# LED-Wiring.net
KiCad netlist of a schematic drawn in EAGLE
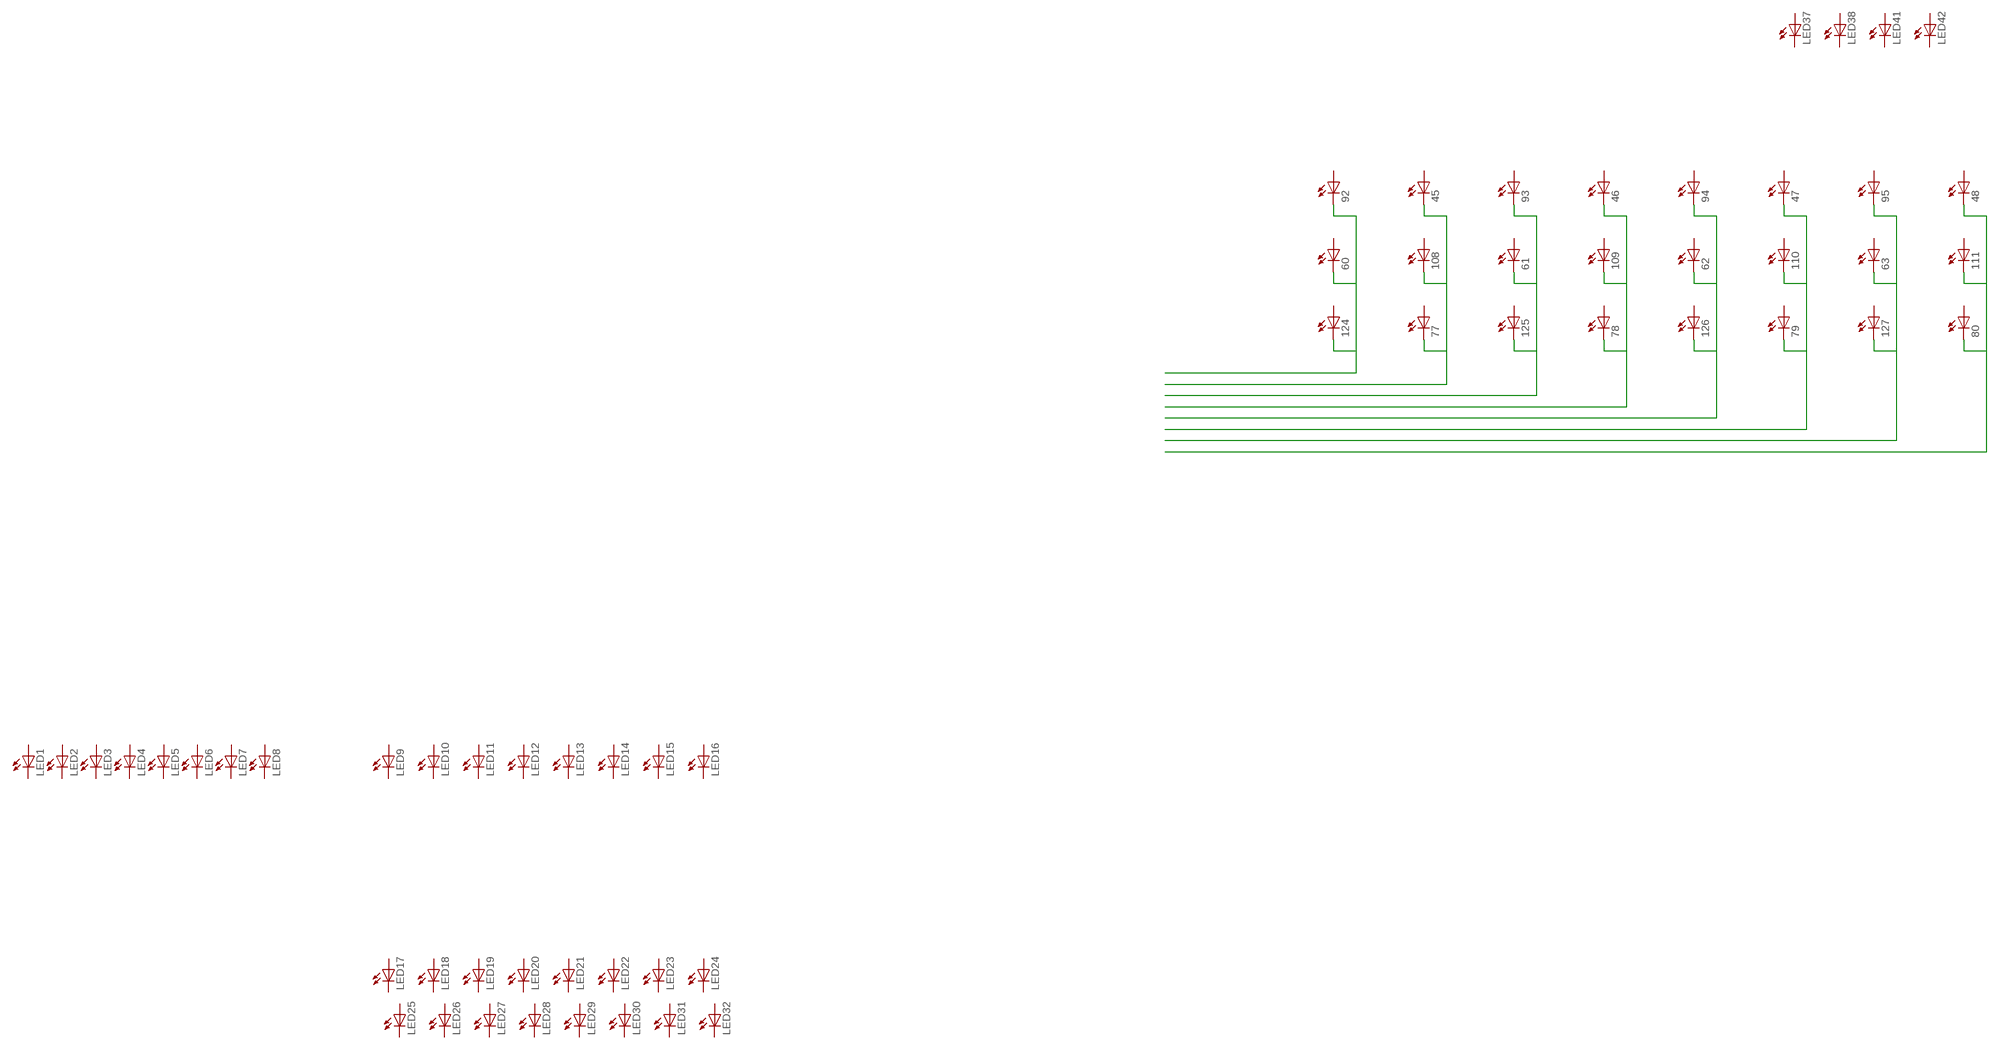
[diagram p0: schematic, sheet 1]

(export (version "E")
  (design (tool "Eeschema 10.0.6"))
  (components
    (comp (ref "45")
      (value "LED")
      (footprint "eagle-import:SMARTLED-TTW")
      (libsource (lib "eagle-import") (part "LED"))
    )
    (comp (ref "46")
      (value "LED")
      (footprint "eagle-import:SMARTLED-TTW")
      (libsource (lib "eagle-import") (part "LED"))
    )
    (comp (ref "47")
      (value "LED")
      (footprint "eagle-import:SMARTLED-TTW")
      (libsource (lib "eagle-import") (part "LED"))
    )
    (comp (ref "48")
      (value "LED")
      (footprint "eagle-import:SMARTLED-TTW")
      (libsource (lib "eagle-import") (part "LED"))
    )
    (comp (ref "60")
      (value "LED")
      (footprint "eagle-import:SMARTLED-TTW")
      (libsource (lib "eagle-import") (part "LED"))
    )
    (comp (ref "61")
      (value "LED")
      (footprint "eagle-import:SMARTLED-TTW")
      (libsource (lib "eagle-import") (part "LED"))
    )
    (comp (ref "62")
      (value "LED")
      (footprint "eagle-import:SMARTLED-TTW")
      (libsource (lib "eagle-import") (part "LED"))
    )
    (comp (ref "63")
      (value "LED")
      (footprint "eagle-import:SMARTLED-TTW")
      (libsource (lib "eagle-import") (part "LED"))
    )
    (comp (ref "77")
      (value "LED")
      (footprint "eagle-import:SMARTLED-TTW")
      (libsource (lib "eagle-import") (part "LED"))
    )
    (comp (ref "78")
      (value "LED")
      (footprint "eagle-import:SMARTLED-TTW")
      (libsource (lib "eagle-import") (part "LED"))
    )
    (comp (ref "79")
      (value "LED")
      (footprint "eagle-import:SMARTLED-TTW")
      (libsource (lib "eagle-import") (part "LED"))
    )
    (comp (ref "80")
      (value "LED")
      (footprint "eagle-import:SMARTLED-TTW")
      (libsource (lib "eagle-import") (part "LED"))
    )
    (comp (ref "92")
      (value "LED")
      (footprint "eagle-import:SMARTLED-TTW")
      (libsource (lib "eagle-import") (part "LED"))
    )
    (comp (ref "93")
      (value "LED")
      (footprint "eagle-import:SMARTLED-TTW")
      (libsource (lib "eagle-import") (part "LED"))
    )
    (comp (ref "94")
      (value "LED")
      (footprint "eagle-import:SMARTLED-TTW")
      (libsource (lib "eagle-import") (part "LED"))
    )
    (comp (ref "95")
      (value "LED")
      (footprint "eagle-import:SMARTLED-TTW")
      (libsource (lib "eagle-import") (part "LED"))
    )
    (comp (ref "108")
      (value "LED")
      (footprint "eagle-import:SMARTLED-TTW")
      (libsource (lib "eagle-import") (part "LED"))
    )
    (comp (ref "109")
      (value "LED")
      (footprint "eagle-import:SMARTLED-TTW")
      (libsource (lib "eagle-import") (part "LED"))
    )
    (comp (ref "110")
      (value "LED")
      (footprint "eagle-import:SMARTLED-TTW")
      (libsource (lib "eagle-import") (part "LED"))
    )
    (comp (ref "111")
      (value "LED")
      (footprint "eagle-import:SMARTLED-TTW")
      (libsource (lib "eagle-import") (part "LED"))
    )
    (comp (ref "124")
      (value "LED")
      (footprint "eagle-import:SMARTLED-TTW")
      (libsource (lib "eagle-import") (part "LED"))
    )
    (comp (ref "125")
      (value "LED")
      (footprint "eagle-import:SMARTLED-TTW")
      (libsource (lib "eagle-import") (part "LED"))
    )
    (comp (ref "126")
      (value "LED")
      (footprint "eagle-import:SMARTLED-TTW")
      (libsource (lib "eagle-import") (part "LED"))
    )
    (comp (ref "127")
      (value "LED")
      (footprint "eagle-import:SMARTLED-TTW")
      (libsource (lib "eagle-import") (part "LED"))
    )
    (comp (ref "LED1")
      (value "LED")
      (footprint "eagle-import:SMARTLED-TTW")
      (libsource (lib "eagle-import") (part "LED"))
    )
    (comp (ref "LED2")
      (value "LED")
      (footprint "eagle-import:SMARTLED-TTW")
      (libsource (lib "eagle-import") (part "LED"))
    )
    (comp (ref "LED3")
      (value "LED")
      (footprint "eagle-import:SMARTLED-TTW")
      (libsource (lib "eagle-import") (part "LED"))
    )
    (comp (ref "LED4")
      (value "LED")
      (footprint "eagle-import:SMARTLED-TTW")
      (libsource (lib "eagle-import") (part "LED"))
    )
    (comp (ref "LED5")
      (value "LED")
      (footprint "eagle-import:SMARTLED-TTW")
      (libsource (lib "eagle-import") (part "LED"))
    )
    (comp (ref "LED6")
      (value "LED")
      (footprint "eagle-import:SMARTLED-TTW")
      (libsource (lib "eagle-import") (part "LED"))
    )
    (comp (ref "LED7")
      (value "LED")
      (footprint "eagle-import:SMARTLED-TTW")
      (libsource (lib "eagle-import") (part "LED"))
    )
    (comp (ref "LED8")
      (value "LED")
      (footprint "eagle-import:SMARTLED-TTW")
      (libsource (lib "eagle-import") (part "LED"))
    )
    (comp (ref "LED9")
      (value "LED")
      (footprint "eagle-import:SMARTLED-TTW")
      (libsource (lib "eagle-import") (part "LED"))
    )
    (comp (ref "LED10")
      (value "LED")
      (footprint "eagle-import:SMARTLED-TTW")
      (libsource (lib "eagle-import") (part "LED"))
    )
    (comp (ref "LED11")
      (value "LED")
      (footprint "eagle-import:SMARTLED-TTW")
      (libsource (lib "eagle-import") (part "LED"))
    )
    (comp (ref "LED12")
      (value "LED")
      (footprint "eagle-import:SMARTLED-TTW")
      (libsource (lib "eagle-import") (part "LED"))
    )
    (comp (ref "LED13")
      (value "LED")
      (footprint "eagle-import:SMARTLED-TTW")
      (libsource (lib "eagle-import") (part "LED"))
    )
    (comp (ref "LED14")
      (value "LED")
      (footprint "eagle-import:SMARTLED-TTW")
      (libsource (lib "eagle-import") (part "LED"))
    )
    (comp (ref "LED15")
      (value "LED")
      (footprint "eagle-import:SMARTLED-TTW")
      (libsource (lib "eagle-import") (part "LED"))
    )
    (comp (ref "LED16")
      (value "LED")
      (footprint "eagle-import:SMARTLED-TTW")
      (libsource (lib "eagle-import") (part "LED"))
    )
    (comp (ref "LED17")
      (value "LED")
      (footprint "eagle-import:SMARTLED-TTW")
      (libsource (lib "eagle-import") (part "LED"))
    )
    (comp (ref "LED18")
      (value "LED")
      (footprint "eagle-import:SMARTLED-TTW")
      (libsource (lib "eagle-import") (part "LED"))
    )
    (comp (ref "LED19")
      (value "LED")
      (footprint "eagle-import:SMARTLED-TTW")
      (libsource (lib "eagle-import") (part "LED"))
    )
    (comp (ref "LED20")
      (value "LED")
      (footprint "eagle-import:SMARTLED-TTW")
      (libsource (lib "eagle-import") (part "LED"))
    )
    (comp (ref "LED21")
      (value "LED")
      (footprint "eagle-import:SMARTLED-TTW")
      (libsource (lib "eagle-import") (part "LED"))
    )
    (comp (ref "LED22")
      (value "LED")
      (footprint "eagle-import:SMARTLED-TTW")
      (libsource (lib "eagle-import") (part "LED"))
    )
    (comp (ref "LED23")
      (value "LED")
      (footprint "eagle-import:SMARTLED-TTW")
      (libsource (lib "eagle-import") (part "LED"))
    )
    (comp (ref "LED24")
      (value "LED")
      (footprint "eagle-import:SMARTLED-TTW")
      (libsource (lib "eagle-import") (part "LED"))
    )
    (comp (ref "LED25")
      (value "LED")
      (footprint "eagle-import:SMARTLED-TTW")
      (libsource (lib "eagle-import") (part "LED"))
    )
    (comp (ref "LED26")
      (value "LED")
      (footprint "eagle-import:SMARTLED-TTW")
      (libsource (lib "eagle-import") (part "LED"))
    )
    (comp (ref "LED27")
      (value "LED")
      (footprint "eagle-import:SMARTLED-TTW")
      (libsource (lib "eagle-import") (part "LED"))
    )
    (comp (ref "LED28")
      (value "LED")
      (footprint "eagle-import:SMARTLED-TTW")
      (libsource (lib "eagle-import") (part "LED"))
    )
    (comp (ref "LED29")
      (value "LED")
      (footprint "eagle-import:SMARTLED-TTW")
      (libsource (lib "eagle-import") (part "LED"))
    )
    (comp (ref "LED30")
      (value "LED")
      (footprint "eagle-import:SMARTLED-TTW")
      (libsource (lib "eagle-import") (part "LED"))
    )
    (comp (ref "LED31")
      (value "LED")
      (footprint "eagle-import:SMARTLED-TTW")
      (libsource (lib "eagle-import") (part "LED"))
    )
    (comp (ref "LED32")
      (value "LED")
      (footprint "eagle-import:SMARTLED-TTW")
      (libsource (lib "eagle-import") (part "LED"))
    )
    (comp (ref "LED37")
      (value "LED")
      (footprint "eagle-import:SMARTLED-TTW")
      (libsource (lib "eagle-import") (part "LED"))
    )
    (comp (ref "LED38")
      (value "LED")
      (footprint "eagle-import:SMARTLED-TTW")
      (libsource (lib "eagle-import") (part "LED"))
    )
    (comp (ref "LED41")
      (value "LED")
      (footprint "eagle-import:SMARTLED-TTW")
      (libsource (lib "eagle-import") (part "LED"))
    )
    (comp (ref "LED42")
      (value "LED")
      (footprint "eagle-import:SMARTLED-TTW")
      (libsource (lib "eagle-import") (part "LED"))
    )
  )
  (nets
    (net (code "1") (name "Net-(108-C)") (class "Default")
      (node (ref "108") (pin "C@1") (pinfunction "C_C@1") (pintype "passive"))
      (node (ref "45") (pin "C@1") (pinfunction "C_C@1") (pintype "passive"))
      (node (ref "77") (pin "C@1") (pinfunction "C_C@1") (pintype "passive"))
    )
    (net (code "2") (name "Net-(109-C)") (class "Default")
      (node (ref "109") (pin "C@1") (pinfunction "C_C@1") (pintype "passive"))
      (node (ref "46") (pin "C@1") (pinfunction "C_C@1") (pintype "passive"))
      (node (ref "78") (pin "C@1") (pinfunction "C_C@1") (pintype "passive"))
    )
    (net (code "3") (name "Net-(110-C)") (class "Default")
      (node (ref "110") (pin "C@1") (pinfunction "C_C@1") (pintype "passive"))
      (node (ref "47") (pin "C@1") (pinfunction "C_C@1") (pintype "passive"))
      (node (ref "79") (pin "C@1") (pinfunction "C_C@1") (pintype "passive"))
    )
    (net (code "4") (name "Net-(111-C)") (class "Default")
      (node (ref "111") (pin "C@1") (pinfunction "C_C@1") (pintype "passive"))
      (node (ref "48") (pin "C@1") (pinfunction "C_C@1") (pintype "passive"))
      (node (ref "80") (pin "C@1") (pinfunction "C_C@1") (pintype "passive"))
    )
    (net (code "5") (name "Net-(124-C)") (class "Default")
      (node (ref "124") (pin "C@1") (pinfunction "C_C@1") (pintype "passive"))
      (node (ref "60") (pin "C@1") (pinfunction "C_C@1") (pintype "passive"))
      (node (ref "92") (pin "C@1") (pinfunction "C_C@1") (pintype "passive"))
    )
    (net (code "6") (name "Net-(125-C)") (class "Default")
      (node (ref "125") (pin "C@1") (pinfunction "C_C@1") (pintype "passive"))
      (node (ref "61") (pin "C@1") (pinfunction "C_C@1") (pintype "passive"))
      (node (ref "93") (pin "C@1") (pinfunction "C_C@1") (pintype "passive"))
    )
    (net (code "7") (name "Net-(126-C)") (class "Default")
      (node (ref "126") (pin "C@1") (pinfunction "C_C@1") (pintype "passive"))
      (node (ref "62") (pin "C@1") (pinfunction "C_C@1") (pintype "passive"))
      (node (ref "94") (pin "C@1") (pinfunction "C_C@1") (pintype "passive"))
    )
    (net (code "8") (name "Net-(127-C)") (class "Default")
      (node (ref "127") (pin "C@1") (pinfunction "C_C@1") (pintype "passive"))
      (node (ref "63") (pin "C@1") (pinfunction "C_C@1") (pintype "passive"))
      (node (ref "95") (pin "C@1") (pinfunction "C_C@1") (pintype "passive"))
    )
    (net (code "9") (name "unconnected-(45-A-PadA@1)") (class "Default")
      (node (ref "45") (pin "A@1") (pinfunction "A_A@1") (pintype "passive"))
    )
    (net (code "10") (name "unconnected-(46-A-PadA@1)") (class "Default")
      (node (ref "46") (pin "A@1") (pinfunction "A_A@1") (pintype "passive"))
    )
    (net (code "11") (name "unconnected-(47-A-PadA@1)") (class "Default")
      (node (ref "47") (pin "A@1") (pinfunction "A_A@1") (pintype "passive"))
    )
    (net (code "12") (name "unconnected-(48-A-PadA@1)") (class "Default")
      (node (ref "48") (pin "A@1") (pinfunction "A_A@1") (pintype "passive"))
    )
    (net (code "13") (name "unconnected-(60-A-PadA@1)") (class "Default")
      (node (ref "60") (pin "A@1") (pinfunction "A_A@1") (pintype "passive"))
    )
    (net (code "14") (name "unconnected-(61-A-PadA@1)") (class "Default")
      (node (ref "61") (pin "A@1") (pinfunction "A_A@1") (pintype "passive"))
    )
    (net (code "15") (name "unconnected-(62-A-PadA@1)") (class "Default")
      (node (ref "62") (pin "A@1") (pinfunction "A_A@1") (pintype "passive"))
    )
    (net (code "16") (name "unconnected-(63-A-PadA@1)") (class "Default")
      (node (ref "63") (pin "A@1") (pinfunction "A_A@1") (pintype "passive"))
    )
    (net (code "17") (name "unconnected-(77-A-PadA@1)") (class "Default")
      (node (ref "77") (pin "A@1") (pinfunction "A_A@1") (pintype "passive"))
    )
    (net (code "18") (name "unconnected-(78-A-PadA@1)") (class "Default")
      (node (ref "78") (pin "A@1") (pinfunction "A_A@1") (pintype "passive"))
    )
    (net (code "19") (name "unconnected-(79-A-PadA@1)") (class "Default")
      (node (ref "79") (pin "A@1") (pinfunction "A_A@1") (pintype "passive"))
    )
    (net (code "20") (name "unconnected-(80-A-PadA@1)") (class "Default")
      (node (ref "80") (pin "A@1") (pinfunction "A_A@1") (pintype "passive"))
    )
    (net (code "21") (name "unconnected-(92-A-PadA@1)") (class "Default")
      (node (ref "92") (pin "A@1") (pinfunction "A_A@1") (pintype "passive"))
    )
    (net (code "22") (name "unconnected-(93-A-PadA@1)") (class "Default")
      (node (ref "93") (pin "A@1") (pinfunction "A_A@1") (pintype "passive"))
    )
    (net (code "23") (name "unconnected-(94-A-PadA@1)") (class "Default")
      (node (ref "94") (pin "A@1") (pinfunction "A_A@1") (pintype "passive"))
    )
    (net (code "24") (name "unconnected-(95-A-PadA@1)") (class "Default")
      (node (ref "95") (pin "A@1") (pinfunction "A_A@1") (pintype "passive"))
    )
    (net (code "25") (name "unconnected-(108-A-PadA@1)") (class "Default")
      (node (ref "108") (pin "A@1") (pinfunction "A_A@1") (pintype "passive"))
    )
    (net (code "26") (name "unconnected-(109-A-PadA@1)") (class "Default")
      (node (ref "109") (pin "A@1") (pinfunction "A_A@1") (pintype "passive"))
    )
    (net (code "27") (name "unconnected-(110-A-PadA@1)") (class "Default")
      (node (ref "110") (pin "A@1") (pinfunction "A_A@1") (pintype "passive"))
    )
    (net (code "28") (name "unconnected-(111-A-PadA@1)") (class "Default")
      (node (ref "111") (pin "A@1") (pinfunction "A_A@1") (pintype "passive"))
    )
    (net (code "29") (name "unconnected-(124-A-PadA@1)") (class "Default")
      (node (ref "124") (pin "A@1") (pinfunction "A_A@1") (pintype "passive"))
    )
    (net (code "30") (name "unconnected-(125-A-PadA@1)") (class "Default")
      (node (ref "125") (pin "A@1") (pinfunction "A_A@1") (pintype "passive"))
    )
    (net (code "31") (name "unconnected-(126-A-PadA@1)") (class "Default")
      (node (ref "126") (pin "A@1") (pinfunction "A_A@1") (pintype "passive"))
    )
    (net (code "32") (name "unconnected-(127-A-PadA@1)") (class "Default")
      (node (ref "127") (pin "A@1") (pinfunction "A_A@1") (pintype "passive"))
    )
    (net (code "33") (name "unconnected-(LED1-A-PadA@1)") (class "Default")
      (node (ref "LED1") (pin "A@1") (pinfunction "A_A@1") (pintype "passive"))
    )
    (net (code "34") (name "unconnected-(LED1-C-PadC@1)") (class "Default")
      (node (ref "LED1") (pin "C@1") (pinfunction "C_C@1") (pintype "passive"))
    )
    (net (code "35") (name "unconnected-(LED2-A-PadA@1)") (class "Default")
      (node (ref "LED2") (pin "A@1") (pinfunction "A_A@1") (pintype "passive"))
    )
    (net (code "36") (name "unconnected-(LED2-C-PadC@1)") (class "Default")
      (node (ref "LED2") (pin "C@1") (pinfunction "C_C@1") (pintype "passive"))
    )
    (net (code "37") (name "unconnected-(LED3-A-PadA@1)") (class "Default")
      (node (ref "LED3") (pin "A@1") (pinfunction "A_A@1") (pintype "passive"))
    )
    (net (code "38") (name "unconnected-(LED3-C-PadC@1)") (class "Default")
      (node (ref "LED3") (pin "C@1") (pinfunction "C_C@1") (pintype "passive"))
    )
    (net (code "39") (name "unconnected-(LED4-A-PadA@1)") (class "Default")
      (node (ref "LED4") (pin "A@1") (pinfunction "A_A@1") (pintype "passive"))
    )
    (net (code "40") (name "unconnected-(LED4-C-PadC@1)") (class "Default")
      (node (ref "LED4") (pin "C@1") (pinfunction "C_C@1") (pintype "passive"))
    )
    (net (code "41") (name "unconnected-(LED5-A-PadA@1)") (class "Default")
      (node (ref "LED5") (pin "A@1") (pinfunction "A_A@1") (pintype "passive"))
    )
    (net (code "42") (name "unconnected-(LED5-C-PadC@1)") (class "Default")
      (node (ref "LED5") (pin "C@1") (pinfunction "C_C@1") (pintype "passive"))
    )
    (net (code "43") (name "unconnected-(LED6-A-PadA@1)") (class "Default")
      (node (ref "LED6") (pin "A@1") (pinfunction "A_A@1") (pintype "passive"))
    )
    (net (code "44") (name "unconnected-(LED6-C-PadC@1)") (class "Default")
      (node (ref "LED6") (pin "C@1") (pinfunction "C_C@1") (pintype "passive"))
    )
    (net (code "45") (name "unconnected-(LED7-A-PadA@1)") (class "Default")
      (node (ref "LED7") (pin "A@1") (pinfunction "A_A@1") (pintype "passive"))
    )
    (net (code "46") (name "unconnected-(LED7-C-PadC@1)") (class "Default")
      (node (ref "LED7") (pin "C@1") (pinfunction "C_C@1") (pintype "passive"))
    )
    (net (code "47") (name "unconnected-(LED8-A-PadA@1)") (class "Default")
      (node (ref "LED8") (pin "A@1") (pinfunction "A_A@1") (pintype "passive"))
    )
    (net (code "48") (name "unconnected-(LED8-C-PadC@1)") (class "Default")
      (node (ref "LED8") (pin "C@1") (pinfunction "C_C@1") (pintype "passive"))
    )
    (net (code "49") (name "unconnected-(LED9-A-PadA@1)") (class "Default")
      (node (ref "LED9") (pin "A@1") (pinfunction "A_A@1") (pintype "passive"))
    )
    (net (code "50") (name "unconnected-(LED9-C-PadC@1)") (class "Default")
      (node (ref "LED9") (pin "C@1") (pinfunction "C_C@1") (pintype "passive"))
    )
    (net (code "51") (name "unconnected-(LED10-A-PadA@1)") (class "Default")
      (node (ref "LED10") (pin "A@1") (pinfunction "A_A@1") (pintype "passive"))
    )
    (net (code "52") (name "unconnected-(LED10-C-PadC@1)") (class "Default")
      (node (ref "LED10") (pin "C@1") (pinfunction "C_C@1") (pintype "passive"))
    )
    (net (code "53") (name "unconnected-(LED11-A-PadA@1)") (class "Default")
      (node (ref "LED11") (pin "A@1") (pinfunction "A_A@1") (pintype "passive"))
    )
    (net (code "54") (name "unconnected-(LED11-C-PadC@1)") (class "Default")
      (node (ref "LED11") (pin "C@1") (pinfunction "C_C@1") (pintype "passive"))
    )
    (net (code "55") (name "unconnected-(LED12-A-PadA@1)") (class "Default")
      (node (ref "LED12") (pin "A@1") (pinfunction "A_A@1") (pintype "passive"))
    )
    (net (code "56") (name "unconnected-(LED12-C-PadC@1)") (class "Default")
      (node (ref "LED12") (pin "C@1") (pinfunction "C_C@1") (pintype "passive"))
    )
    (net (code "57") (name "unconnected-(LED13-A-PadA@1)") (class "Default")
      (node (ref "LED13") (pin "A@1") (pinfunction "A_A@1") (pintype "passive"))
    )
    (net (code "58") (name "unconnected-(LED13-C-PadC@1)") (class "Default")
      (node (ref "LED13") (pin "C@1") (pinfunction "C_C@1") (pintype "passive"))
    )
    (net (code "59") (name "unconnected-(LED14-A-PadA@1)") (class "Default")
      (node (ref "LED14") (pin "A@1") (pinfunction "A_A@1") (pintype "passive"))
    )
    (net (code "60") (name "unconnected-(LED14-C-PadC@1)") (class "Default")
      (node (ref "LED14") (pin "C@1") (pinfunction "C_C@1") (pintype "passive"))
    )
    (net (code "61") (name "unconnected-(LED15-A-PadA@1)") (class "Default")
      (node (ref "LED15") (pin "A@1") (pinfunction "A_A@1") (pintype "passive"))
    )
    (net (code "62") (name "unconnected-(LED15-C-PadC@1)") (class "Default")
      (node (ref "LED15") (pin "C@1") (pinfunction "C_C@1") (pintype "passive"))
    )
    (net (code "63") (name "unconnected-(LED16-A-PadA@1)") (class "Default")
      (node (ref "LED16") (pin "A@1") (pinfunction "A_A@1") (pintype "passive"))
    )
    (net (code "64") (name "unconnected-(LED16-C-PadC@1)") (class "Default")
      (node (ref "LED16") (pin "C@1") (pinfunction "C_C@1") (pintype "passive"))
    )
    (net (code "65") (name "unconnected-(LED17-A-PadA@1)") (class "Default")
      (node (ref "LED17") (pin "A@1") (pinfunction "A_A@1") (pintype "passive"))
    )
    (net (code "66") (name "unconnected-(LED17-C-PadC@1)") (class "Default")
      (node (ref "LED17") (pin "C@1") (pinfunction "C_C@1") (pintype "passive"))
    )
    (net (code "67") (name "unconnected-(LED18-A-PadA@1)") (class "Default")
      (node (ref "LED18") (pin "A@1") (pinfunction "A_A@1") (pintype "passive"))
    )
    (net (code "68") (name "unconnected-(LED18-C-PadC@1)") (class "Default")
      (node (ref "LED18") (pin "C@1") (pinfunction "C_C@1") (pintype "passive"))
    )
    (net (code "69") (name "unconnected-(LED19-A-PadA@1)") (class "Default")
      (node (ref "LED19") (pin "A@1") (pinfunction "A_A@1") (pintype "passive"))
    )
    (net (code "70") (name "unconnected-(LED19-C-PadC@1)") (class "Default")
      (node (ref "LED19") (pin "C@1") (pinfunction "C_C@1") (pintype "passive"))
    )
    (net (code "71") (name "unconnected-(LED20-A-PadA@1)") (class "Default")
      (node (ref "LED20") (pin "A@1") (pinfunction "A_A@1") (pintype "passive"))
    )
    (net (code "72") (name "unconnected-(LED20-C-PadC@1)") (class "Default")
      (node (ref "LED20") (pin "C@1") (pinfunction "C_C@1") (pintype "passive"))
    )
    (net (code "73") (name "unconnected-(LED21-A-PadA@1)") (class "Default")
      (node (ref "LED21") (pin "A@1") (pinfunction "A_A@1") (pintype "passive"))
    )
    (net (code "74") (name "unconnected-(LED21-C-PadC@1)") (class "Default")
      (node (ref "LED21") (pin "C@1") (pinfunction "C_C@1") (pintype "passive"))
    )
    (net (code "75") (name "unconnected-(LED22-A-PadA@1)") (class "Default")
      (node (ref "LED22") (pin "A@1") (pinfunction "A_A@1") (pintype "passive"))
    )
    (net (code "76") (name "unconnected-(LED22-C-PadC@1)") (class "Default")
      (node (ref "LED22") (pin "C@1") (pinfunction "C_C@1") (pintype "passive"))
    )
    (net (code "77") (name "unconnected-(LED23-A-PadA@1)") (class "Default")
      (node (ref "LED23") (pin "A@1") (pinfunction "A_A@1") (pintype "passive"))
    )
    (net (code "78") (name "unconnected-(LED23-C-PadC@1)") (class "Default")
      (node (ref "LED23") (pin "C@1") (pinfunction "C_C@1") (pintype "passive"))
    )
    (net (code "79") (name "unconnected-(LED24-A-PadA@1)") (class "Default")
      (node (ref "LED24") (pin "A@1") (pinfunction "A_A@1") (pintype "passive"))
    )
    (net (code "80") (name "unconnected-(LED24-C-PadC@1)") (class "Default")
      (node (ref "LED24") (pin "C@1") (pinfunction "C_C@1") (pintype "passive"))
    )
    (net (code "81") (name "unconnected-(LED25-A-PadA@1)") (class "Default")
      (node (ref "LED25") (pin "A@1") (pinfunction "A_A@1") (pintype "passive"))
    )
    (net (code "82") (name "unconnected-(LED25-C-PadC@1)") (class "Default")
      (node (ref "LED25") (pin "C@1") (pinfunction "C_C@1") (pintype "passive"))
    )
    (net (code "83") (name "unconnected-(LED26-A-PadA@1)") (class "Default")
      (node (ref "LED26") (pin "A@1") (pinfunction "A_A@1") (pintype "passive"))
    )
    (net (code "84") (name "unconnected-(LED26-C-PadC@1)") (class "Default")
      (node (ref "LED26") (pin "C@1") (pinfunction "C_C@1") (pintype "passive"))
    )
    (net (code "85") (name "unconnected-(LED27-A-PadA@1)") (class "Default")
      (node (ref "LED27") (pin "A@1") (pinfunction "A_A@1") (pintype "passive"))
    )
    (net (code "86") (name "unconnected-(LED27-C-PadC@1)") (class "Default")
      (node (ref "LED27") (pin "C@1") (pinfunction "C_C@1") (pintype "passive"))
    )
    (net (code "87") (name "unconnected-(LED28-A-PadA@1)") (class "Default")
      (node (ref "LED28") (pin "A@1") (pinfunction "A_A@1") (pintype "passive"))
    )
    (net (code "88") (name "unconnected-(LED28-C-PadC@1)") (class "Default")
      (node (ref "LED28") (pin "C@1") (pinfunction "C_C@1") (pintype "passive"))
    )
    (net (code "89") (name "unconnected-(LED29-A-PadA@1)") (class "Default")
      (node (ref "LED29") (pin "A@1") (pinfunction "A_A@1") (pintype "passive"))
    )
    (net (code "90") (name "unconnected-(LED29-C-PadC@1)") (class "Default")
      (node (ref "LED29") (pin "C@1") (pinfunction "C_C@1") (pintype "passive"))
    )
    (net (code "91") (name "unconnected-(LED30-A-PadA@1)") (class "Default")
      (node (ref "LED30") (pin "A@1") (pinfunction "A_A@1") (pintype "passive"))
    )
    (net (code "92") (name "unconnected-(LED30-C-PadC@1)") (class "Default")
      (node (ref "LED30") (pin "C@1") (pinfunction "C_C@1") (pintype "passive"))
    )
    (net (code "93") (name "unconnected-(LED31-A-PadA@1)") (class "Default")
      (node (ref "LED31") (pin "A@1") (pinfunction "A_A@1") (pintype "passive"))
    )
    (net (code "94") (name "unconnected-(LED31-C-PadC@1)") (class "Default")
      (node (ref "LED31") (pin "C@1") (pinfunction "C_C@1") (pintype "passive"))
    )
    (net (code "95") (name "unconnected-(LED32-A-PadA@1)") (class "Default")
      (node (ref "LED32") (pin "A@1") (pinfunction "A_A@1") (pintype "passive"))
    )
    (net (code "96") (name "unconnected-(LED32-C-PadC@1)") (class "Default")
      (node (ref "LED32") (pin "C@1") (pinfunction "C_C@1") (pintype "passive"))
    )
    (net (code "97") (name "unconnected-(LED37-A-PadA@1)") (class "Default")
      (node (ref "LED37") (pin "A@1") (pinfunction "A_A@1") (pintype "passive"))
    )
    (net (code "98") (name "unconnected-(LED37-C-PadC@1)") (class "Default")
      (node (ref "LED37") (pin "C@1") (pinfunction "C_C@1") (pintype "passive"))
    )
    (net (code "99") (name "unconnected-(LED38-A-PadA@1)") (class "Default")
      (node (ref "LED38") (pin "A@1") (pinfunction "A_A@1") (pintype "passive"))
    )
    (net (code "100") (name "unconnected-(LED38-C-PadC@1)") (class "Default")
      (node (ref "LED38") (pin "C@1") (pinfunction "C_C@1") (pintype "passive"))
    )
    (net (code "101") (name "unconnected-(LED41-A-PadA@1)") (class "Default")
      (node (ref "LED41") (pin "A@1") (pinfunction "A_A@1") (pintype "passive"))
    )
    (net (code "102") (name "unconnected-(LED41-C-PadC@1)") (class "Default")
      (node (ref "LED41") (pin "C@1") (pinfunction "C_C@1") (pintype "passive"))
    )
    (net (code "103") (name "unconnected-(LED42-A-PadA@1)") (class "Default")
      (node (ref "LED42") (pin "A@1") (pinfunction "A_A@1") (pintype "passive"))
    )
    (net (code "104") (name "unconnected-(LED42-C-PadC@1)") (class "Default")
      (node (ref "LED42") (pin "C@1") (pinfunction "C_C@1") (pintype "passive"))
    )
  )
)
